# nixie_tube.net
KiCad netlist of a schematic drawn in Altium Designer
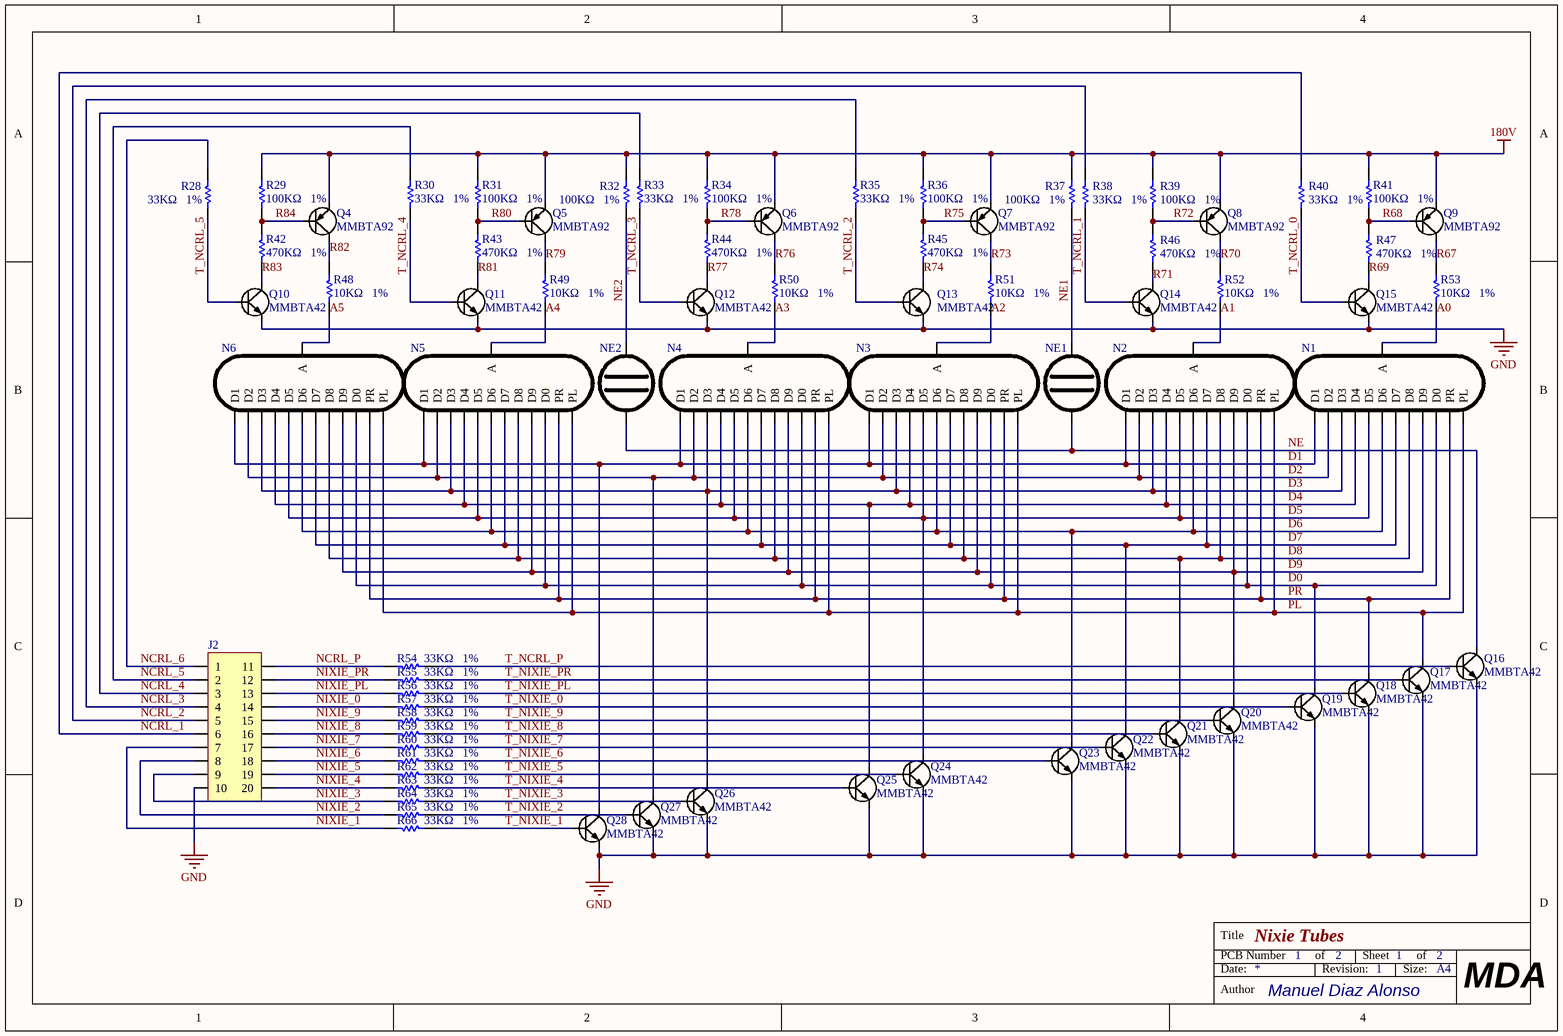
[diagram p0: nixie_tube.SchDoc]

(export (version "E")
  (design (tool "Eeschema 10.0.6"))
  (components
    (comp (ref "J2")
      (value "PIN_2X10")
      (footprint "PIN_2X10_HDR")
      (description "TSW-110-15-F-D-LL")
      (libsource (lib "Nixielib") (part "PIN_2X10"))
    )
    (comp (ref "N1")
      (value "NIXIE-IN14")
      (footprint "NIXIE_IN-14")
      (libsource (lib "MyLib") (part "NIXIE-IN14"))
    )
    (comp (ref "N2")
      (value "NIXIE-IN14")
      (footprint "NIXIE_IN-14")
      (libsource (lib "MyLib") (part "NIXIE-IN14"))
    )
    (comp (ref "N3")
      (value "NIXIE-IN14")
      (footprint "NIXIE_IN-14")
      (libsource (lib "MyLib") (part "NIXIE-IN14"))
    )
    (comp (ref "N4")
      (value "NIXIE-IN14")
      (footprint "NIXIE_IN-14")
      (libsource (lib "MyLib") (part "NIXIE-IN14"))
    )
    (comp (ref "N5")
      (value "NIXIE-IN14")
      (footprint "NIXIE_IN-14")
      (libsource (lib "MyLib") (part "NIXIE-IN14"))
    )
    (comp (ref "N6")
      (value "NIXIE-IN14")
      (footprint "NIXIE_IN-14")
      (libsource (lib "MyLib") (part "NIXIE-IN14"))
    )
    (comp (ref "NE1")
      (value "NIXIE-IN3")
      (footprint "NIXIE_IN-3")
      (libsource (lib "MyLib") (part "NIXIE-IN3"))
    )
    (comp (ref "NE2")
      (value "NIXIE-IN3")
      (footprint "NIXIE_IN-3")
      (libsource (lib "MyLib") (part "NIXIE-IN3"))
    )
    (comp (ref "Q4") (value "MMBTA92") (footprint "SOT-23") (libsource (lib "Nixielib") (part "PNP")))
    (comp (ref "Q5") (value "MMBTA92") (footprint "SOT-23") (libsource (lib "Nixielib") (part "PNP")))
    (comp (ref "Q6") (value "MMBTA92") (footprint "SOT-23") (libsource (lib "Nixielib") (part "PNP")))
    (comp (ref "Q7") (value "MMBTA92") (footprint "SOT-23") (libsource (lib "Nixielib") (part "PNP")))
    (comp (ref "Q8") (value "MMBTA92") (footprint "SOT-23") (libsource (lib "Nixielib") (part "PNP")))
    (comp (ref "Q9") (value "MMBTA92") (footprint "SOT-23") (libsource (lib "Nixielib") (part "PNP")))
    (comp (ref "Q10") (value "MMBTA42") (footprint "SOT-23") (libsource (lib "Nixielib") (part "NPN")))
    (comp (ref "Q11") (value "MMBTA42") (footprint "SOT-23") (libsource (lib "Nixielib") (part "NPN")))
    (comp (ref "Q12") (value "MMBTA42") (footprint "SOT-23") (libsource (lib "Nixielib") (part "NPN")))
    (comp (ref "Q13") (value "MMBTA42") (footprint "SOT-23") (libsource (lib "Nixielib") (part "NPN")))
    (comp (ref "Q14") (value "MMBTA42") (footprint "SOT-23") (libsource (lib "Nixielib") (part "NPN")))
    (comp (ref "Q15") (value "MMBTA42") (footprint "SOT-23") (libsource (lib "Nixielib") (part "NPN")))
    (comp (ref "Q16") (value "MMBTA42") (footprint "SOT-23") (libsource (lib "Nixielib") (part "NPN")))
    (comp (ref "Q17") (value "MMBTA42") (footprint "SOT-23") (libsource (lib "Nixielib") (part "NPN")))
    (comp (ref "Q18") (value "MMBTA42") (footprint "SOT-23") (libsource (lib "Nixielib") (part "NPN")))
    (comp (ref "Q19") (value "MMBTA42") (footprint "SOT-23") (libsource (lib "Nixielib") (part "NPN")))
    (comp (ref "Q20") (value "MMBTA42") (footprint "SOT-23") (libsource (lib "Nixielib") (part "NPN")))
    (comp (ref "Q21") (value "MMBTA42") (footprint "SOT-23") (libsource (lib "Nixielib") (part "NPN")))
    (comp (ref "Q22") (value "MMBTA42") (footprint "SOT-23") (libsource (lib "Nixielib") (part "NPN")))
    (comp (ref "Q23") (value "MMBTA42") (footprint "SOT-23") (libsource (lib "Nixielib") (part "NPN")))
    (comp (ref "Q24") (value "MMBTA42") (footprint "SOT-23") (libsource (lib "Nixielib") (part "NPN")))
    (comp (ref "Q25") (value "MMBTA42") (footprint "SOT-23") (libsource (lib "Nixielib") (part "NPN")))
    (comp (ref "Q26") (value "MMBTA42") (footprint "SOT-23") (libsource (lib "Nixielib") (part "NPN")))
    (comp (ref "Q27") (value "MMBTA42") (footprint "SOT-23") (libsource (lib "Nixielib") (part "NPN")))
    (comp (ref "Q28") (value "MMBTA42") (footprint "SOT-23") (libsource (lib "Nixielib") (part "NPN")))
    (comp (ref "R28") (value "33KΩ   1%") (footprint "0603") (libsource (lib "Nixielib") (part "RES")))
    (comp (ref "R29") (value "100KΩ   1%") (footprint "0603") (libsource (lib "Nixielib") (part "RES")))
    (comp (ref "R30") (value "33KΩ   1%") (footprint "0603") (libsource (lib "Nixielib") (part "RES")))
    (comp (ref "R31") (value "100KΩ   1%") (footprint "0603") (libsource (lib "Nixielib") (part "RES")))
    (comp (ref "R32") (value "100KΩ   1%") (footprint "0603") (libsource (lib "Nixielib") (part "RES")))
    (comp (ref "R33") (value "33KΩ   1%") (footprint "0603") (libsource (lib "Nixielib") (part "RES")))
    (comp (ref "R34") (value "100KΩ   1%") (footprint "0603") (libsource (lib "Nixielib") (part "RES")))
    (comp (ref "R35") (value "33KΩ   1%") (footprint "0603") (libsource (lib "Nixielib") (part "RES")))
    (comp (ref "R36") (value "100KΩ   1%") (footprint "0603") (libsource (lib "Nixielib") (part "RES")))
    (comp (ref "R37") (value "100KΩ   1%") (footprint "0603") (libsource (lib "Nixielib") (part "RES")))
    (comp (ref "R38") (value "33KΩ   1%") (footprint "0603") (libsource (lib "Nixielib") (part "RES")))
    (comp (ref "R39") (value "100KΩ   1%") (footprint "0603") (libsource (lib "Nixielib") (part "RES")))
    (comp (ref "R40") (value "33KΩ   1%") (footprint "0603") (libsource (lib "Nixielib") (part "RES")))
    (comp (ref "R41") (value "100KΩ   1%") (footprint "0603") (libsource (lib "Nixielib") (part "RES")))
    (comp (ref "R42") (value "470KΩ   1%") (footprint "0603") (libsource (lib "Nixielib") (part "RES")))
    (comp (ref "R43") (value "470KΩ   1%") (footprint "0603") (libsource (lib "Nixielib") (part "RES")))
    (comp (ref "R44") (value "470KΩ   1%") (footprint "0603") (libsource (lib "Nixielib") (part "RES")))
    (comp (ref "R45") (value "470KΩ   1%") (footprint "0603") (libsource (lib "Nixielib") (part "RES")))
    (comp (ref "R46") (value "470KΩ   1%") (footprint "0603") (libsource (lib "Nixielib") (part "RES")))
    (comp (ref "R47") (value "470KΩ   1%") (footprint "0603") (libsource (lib "Nixielib") (part "RES")))
    (comp (ref "R48") (value "10KΩ   1%") (footprint "0603") (libsource (lib "Nixielib") (part "RES")))
    (comp (ref "R49") (value "10KΩ   1%") (footprint "0603") (libsource (lib "Nixielib") (part "RES")))
    (comp (ref "R50") (value "10KΩ   1%") (footprint "0603") (libsource (lib "Nixielib") (part "RES")))
    (comp (ref "R51") (value "10KΩ   1%") (footprint "0603") (libsource (lib "Nixielib") (part "RES")))
    (comp (ref "R52") (value "10KΩ   1%") (footprint "0603") (libsource (lib "Nixielib") (part "RES")))
    (comp (ref "R53") (value "10KΩ   1%") (footprint "0603") (libsource (lib "Nixielib") (part "RES")))
    (comp (ref "R54") (value "33KΩ   1%") (footprint "0603") (libsource (lib "Nixielib") (part "RES")))
    (comp (ref "R55") (value "33KΩ   1%") (footprint "0603") (libsource (lib "Nixielib") (part "RES")))
    (comp (ref "R56") (value "33KΩ   1%") (footprint "0603") (libsource (lib "Nixielib") (part "RES")))
    (comp (ref "R57") (value "33KΩ   1%") (footprint "0603") (libsource (lib "Nixielib") (part "RES")))
    (comp (ref "R58") (value "33KΩ   1%") (footprint "0603") (libsource (lib "Nixielib") (part "RES")))
    (comp (ref "R59") (value "33KΩ   1%") (footprint "0603") (libsource (lib "Nixielib") (part "RES")))
    (comp (ref "R60") (value "33KΩ   1%") (footprint "0603") (libsource (lib "Nixielib") (part "RES")))
    (comp (ref "R61") (value "33KΩ   1%") (footprint "0603") (libsource (lib "Nixielib") (part "RES")))
    (comp (ref "R62") (value "33KΩ   1%") (footprint "0603") (libsource (lib "Nixielib") (part "RES")))
    (comp (ref "R63") (value "33KΩ   1%") (footprint "0603") (libsource (lib "Nixielib") (part "RES")))
    (comp (ref "R64") (value "33KΩ   1%") (footprint "0603") (libsource (lib "Nixielib") (part "RES")))
    (comp (ref "R65") (value "33KΩ   1%") (footprint "0603") (libsource (lib "Nixielib") (part "RES")))
    (comp (ref "R66") (value "33KΩ   1%") (footprint "0603") (libsource (lib "Nixielib") (part "RES")))
  )
  (nets
    (net (code "1") (name "/A0") (class "Default")
      (node (ref "N1") (pin "1") (pinfunction "A_1") (pintype "passive"))
      (node (ref "R53") (pin "1") (pinfunction "1_1") (pintype "passive"))
    )
    (net (code "2") (name "/A1") (class "Default")
      (node (ref "N2") (pin "1") (pinfunction "A_1") (pintype "passive"))
      (node (ref "R52") (pin "1") (pinfunction "1_1") (pintype "passive"))
    )
    (net (code "3") (name "/A2") (class "Default")
      (node (ref "N3") (pin "1") (pinfunction "A_1") (pintype "passive"))
      (node (ref "R51") (pin "1") (pinfunction "1_1") (pintype "passive"))
    )
    (net (code "4") (name "/A3") (class "Default")
      (node (ref "N4") (pin "1") (pinfunction "A_1") (pintype "passive"))
      (node (ref "R50") (pin "1") (pinfunction "1_1") (pintype "passive"))
    )
    (net (code "5") (name "/A4") (class "Default")
      (node (ref "N5") (pin "1") (pinfunction "A_1") (pintype "passive"))
      (node (ref "R49") (pin "1") (pinfunction "1_1") (pintype "passive"))
    )
    (net (code "6") (name "/A5") (class "Default")
      (node (ref "N6") (pin "1") (pinfunction "A_1") (pintype "passive"))
      (node (ref "R48") (pin "1") (pinfunction "1_1") (pintype "passive"))
    )
    (net (code "7") (name "/D0") (class "Default")
      (node (ref "N1") (pin "12") (pinfunction "D0_12") (pintype "passive"))
      (node (ref "N2") (pin "12") (pinfunction "D0_12") (pintype "passive"))
      (node (ref "N3") (pin "12") (pinfunction "D0_12") (pintype "passive"))
      (node (ref "N4") (pin "12") (pinfunction "D0_12") (pintype "passive"))
      (node (ref "N5") (pin "12") (pinfunction "D0_12") (pintype "passive"))
      (node (ref "N6") (pin "12") (pinfunction "D0_12") (pintype "passive"))
      (node (ref "Q19") (pin "3") (pinfunction "C_3") (pintype "passive"))
    )
    (net (code "8") (name "/D1") (class "Default")
      (node (ref "N1") (pin "3") (pinfunction "D1_3") (pintype "passive"))
      (node (ref "N2") (pin "3") (pinfunction "D1_3") (pintype "passive"))
      (node (ref "N3") (pin "3") (pinfunction "D1_3") (pintype "passive"))
      (node (ref "N4") (pin "3") (pinfunction "D1_3") (pintype "passive"))
      (node (ref "N5") (pin "3") (pinfunction "D1_3") (pintype "passive"))
      (node (ref "N6") (pin "3") (pinfunction "D1_3") (pintype "passive"))
      (node (ref "Q28") (pin "3") (pinfunction "C_3") (pintype "passive"))
    )
    (net (code "9") (name "/D2") (class "Default")
      (node (ref "N1") (pin "4") (pinfunction "D2_4") (pintype "passive"))
      (node (ref "N2") (pin "4") (pinfunction "D2_4") (pintype "passive"))
      (node (ref "N3") (pin "4") (pinfunction "D2_4") (pintype "passive"))
      (node (ref "N4") (pin "4") (pinfunction "D2_4") (pintype "passive"))
      (node (ref "N5") (pin "4") (pinfunction "D2_4") (pintype "passive"))
      (node (ref "N6") (pin "4") (pinfunction "D2_4") (pintype "passive"))
      (node (ref "Q27") (pin "3") (pinfunction "C_3") (pintype "passive"))
    )
    (net (code "10") (name "/D3") (class "Default")
      (node (ref "N1") (pin "5") (pinfunction "D3_5") (pintype "passive"))
      (node (ref "N2") (pin "5") (pinfunction "D3_5") (pintype "passive"))
      (node (ref "N3") (pin "5") (pinfunction "D3_5") (pintype "passive"))
      (node (ref "N4") (pin "5") (pinfunction "D3_5") (pintype "passive"))
      (node (ref "N5") (pin "5") (pinfunction "D3_5") (pintype "passive"))
      (node (ref "N6") (pin "5") (pinfunction "D3_5") (pintype "passive"))
      (node (ref "Q26") (pin "3") (pinfunction "C_3") (pintype "passive"))
    )
    (net (code "11") (name "/D4") (class "Default")
      (node (ref "N1") (pin "6") (pinfunction "D4_6") (pintype "passive"))
      (node (ref "N2") (pin "6") (pinfunction "D4_6") (pintype "passive"))
      (node (ref "N3") (pin "6") (pinfunction "D4_6") (pintype "passive"))
      (node (ref "N4") (pin "6") (pinfunction "D4_6") (pintype "passive"))
      (node (ref "N5") (pin "6") (pinfunction "D4_6") (pintype "passive"))
      (node (ref "N6") (pin "6") (pinfunction "D4_6") (pintype "passive"))
      (node (ref "Q25") (pin "3") (pinfunction "C_3") (pintype "passive"))
    )
    (net (code "12") (name "/D5") (class "Default")
      (node (ref "N1") (pin "7") (pinfunction "D5_7") (pintype "passive"))
      (node (ref "N2") (pin "7") (pinfunction "D5_7") (pintype "passive"))
      (node (ref "N3") (pin "7") (pinfunction "D5_7") (pintype "passive"))
      (node (ref "N4") (pin "7") (pinfunction "D5_7") (pintype "passive"))
      (node (ref "N5") (pin "7") (pinfunction "D5_7") (pintype "passive"))
      (node (ref "N6") (pin "7") (pinfunction "D5_7") (pintype "passive"))
      (node (ref "Q24") (pin "3") (pinfunction "C_3") (pintype "passive"))
    )
    (net (code "13") (name "/D6") (class "Default")
      (node (ref "N1") (pin "8") (pinfunction "D6_8") (pintype "passive"))
      (node (ref "N2") (pin "8") (pinfunction "D6_8") (pintype "passive"))
      (node (ref "N3") (pin "8") (pinfunction "D6_8") (pintype "passive"))
      (node (ref "N4") (pin "8") (pinfunction "D6_8") (pintype "passive"))
      (node (ref "N5") (pin "8") (pinfunction "D6_8") (pintype "passive"))
      (node (ref "N6") (pin "8") (pinfunction "D6_8") (pintype "passive"))
      (node (ref "Q23") (pin "3") (pinfunction "C_3") (pintype "passive"))
    )
    (net (code "14") (name "/D7") (class "Default")
      (node (ref "N1") (pin "9") (pinfunction "D7_9") (pintype "passive"))
      (node (ref "N2") (pin "9") (pinfunction "D7_9") (pintype "passive"))
      (node (ref "N3") (pin "9") (pinfunction "D7_9") (pintype "passive"))
      (node (ref "N4") (pin "9") (pinfunction "D7_9") (pintype "passive"))
      (node (ref "N5") (pin "9") (pinfunction "D7_9") (pintype "passive"))
      (node (ref "N6") (pin "9") (pinfunction "D7_9") (pintype "passive"))
      (node (ref "Q22") (pin "3") (pinfunction "C_3") (pintype "passive"))
    )
    (net (code "15") (name "/D8") (class "Default")
      (node (ref "N1") (pin "10") (pinfunction "D8_10") (pintype "passive"))
      (node (ref "N2") (pin "10") (pinfunction "D8_10") (pintype "passive"))
      (node (ref "N3") (pin "10") (pinfunction "D8_10") (pintype "passive"))
      (node (ref "N4") (pin "10") (pinfunction "D8_10") (pintype "passive"))
      (node (ref "N5") (pin "10") (pinfunction "D8_10") (pintype "passive"))
      (node (ref "N6") (pin "10") (pinfunction "D8_10") (pintype "passive"))
      (node (ref "Q21") (pin "3") (pinfunction "C_3") (pintype "passive"))
    )
    (net (code "16") (name "/D9") (class "Default")
      (node (ref "N1") (pin "11") (pinfunction "D9_11") (pintype "passive"))
      (node (ref "N2") (pin "11") (pinfunction "D9_11") (pintype "passive"))
      (node (ref "N3") (pin "11") (pinfunction "D9_11") (pintype "passive"))
      (node (ref "N4") (pin "11") (pinfunction "D9_11") (pintype "passive"))
      (node (ref "N5") (pin "11") (pinfunction "D9_11") (pintype "passive"))
      (node (ref "N6") (pin "11") (pinfunction "D9_11") (pintype "passive"))
      (node (ref "Q20") (pin "3") (pinfunction "C_3") (pintype "passive"))
    )
    (net (code "17") (name "/NCRL_1") (class "Default")
      (node (ref "J2") (pin "6") (pinfunction "6_6") (pintype "passive"))
      (node (ref "R40") (pin "1") (pinfunction "1_1") (pintype "passive"))
    )
    (net (code "18") (name "/NCRL_2") (class "Default")
      (node (ref "J2") (pin "5") (pinfunction "5_5") (pintype "passive"))
      (node (ref "R38") (pin "2") (pinfunction "2_2") (pintype "passive"))
    )
    (net (code "19") (name "/NCRL_3") (class "Default")
      (node (ref "J2") (pin "4") (pinfunction "4_4") (pintype "passive"))
      (node (ref "R35") (pin "2") (pinfunction "2_2") (pintype "passive"))
    )
    (net (code "20") (name "/NCRL_4") (class "Default")
      (node (ref "J2") (pin "3") (pinfunction "3_3") (pintype "passive"))
      (node (ref "R33") (pin "1") (pinfunction "1_1") (pintype "passive"))
    )
    (net (code "21") (name "/NCRL_5") (class "Default")
      (node (ref "J2") (pin "2") (pinfunction "2_2") (pintype "passive"))
      (node (ref "R30") (pin "2") (pinfunction "2_2") (pintype "passive"))
    )
    (net (code "22") (name "/NCRL_6") (class "Default")
      (node (ref "J2") (pin "1") (pinfunction "1_1") (pintype "passive"))
      (node (ref "R28") (pin "2") (pinfunction "2_2") (pintype "passive"))
    )
    (net (code "23") (name "/NCRL_P") (class "Default")
      (node (ref "J2") (pin "11") (pinfunction "11_11") (pintype "passive"))
      (node (ref "R54") (pin "1") (pinfunction "1_1") (pintype "passive"))
    )
    (net (code "24") (name "/NE") (class "Default")
      (node (ref "NE1") (pin "2") (pinfunction "2_2") (pintype "passive"))
      (node (ref "NE2") (pin "2") (pinfunction "2_2") (pintype "passive"))
      (node (ref "Q16") (pin "3") (pinfunction "C_3") (pintype "passive"))
    )
    (net (code "25") (name "/NE1") (class "Default")
      (node (ref "NE1") (pin "1") (pinfunction "1_1") (pintype "passive"))
      (node (ref "R37") (pin "1") (pinfunction "1_1") (pintype "passive"))
    )
    (net (code "26") (name "/NE2") (class "Default")
      (node (ref "NE2") (pin "1") (pinfunction "1_1") (pintype "passive"))
      (node (ref "R32") (pin "1") (pinfunction "1_1") (pintype "passive"))
    )
    (net (code "27") (name "/NIXIE_0") (class "Default")
      (node (ref "J2") (pin "14") (pinfunction "14_14") (pintype "passive"))
      (node (ref "R57") (pin "1") (pinfunction "1_1") (pintype "passive"))
    )
    (net (code "28") (name "/NIXIE_1") (class "Default")
      (node (ref "J2") (pin "7") (pinfunction "7_7") (pintype "passive"))
      (node (ref "R66") (pin "1") (pinfunction "1_1") (pintype "passive"))
    )
    (net (code "29") (name "/NIXIE_2") (class "Default")
      (node (ref "J2") (pin "8") (pinfunction "8_8") (pintype "passive"))
      (node (ref "R65") (pin "1") (pinfunction "1_1") (pintype "passive"))
    )
    (net (code "30") (name "/NIXIE_3") (class "Default")
      (node (ref "J2") (pin "9") (pinfunction "9_9") (pintype "passive"))
      (node (ref "R64") (pin "1") (pinfunction "1_1") (pintype "passive"))
    )
    (net (code "31") (name "/NIXIE_4") (class "Default")
      (node (ref "J2") (pin "20") (pinfunction "20_20") (pintype "passive"))
      (node (ref "R63") (pin "1") (pinfunction "1_1") (pintype "passive"))
    )
    (net (code "32") (name "/NIXIE_5") (class "Default")
      (node (ref "J2") (pin "19") (pinfunction "19_19") (pintype "passive"))
      (node (ref "R62") (pin "1") (pinfunction "1_1") (pintype "passive"))
    )
    (net (code "33") (name "/NIXIE_6") (class "Default")
      (node (ref "J2") (pin "18") (pinfunction "18_18") (pintype "passive"))
      (node (ref "R61") (pin "1") (pinfunction "1_1") (pintype "passive"))
    )
    (net (code "34") (name "/NIXIE_7") (class "Default")
      (node (ref "J2") (pin "17") (pinfunction "17_17") (pintype "passive"))
      (node (ref "R60") (pin "1") (pinfunction "1_1") (pintype "passive"))
    )
    (net (code "35") (name "/NIXIE_8") (class "Default")
      (node (ref "J2") (pin "16") (pinfunction "16_16") (pintype "passive"))
      (node (ref "R59") (pin "1") (pinfunction "1_1") (pintype "passive"))
    )
    (net (code "36") (name "/NIXIE_9") (class "Default")
      (node (ref "J2") (pin "15") (pinfunction "15_15") (pintype "passive"))
      (node (ref "R58") (pin "1") (pinfunction "1_1") (pintype "passive"))
    )
    (net (code "37") (name "/NIXIE_PL") (class "Default")
      (node (ref "J2") (pin "13") (pinfunction "13_13") (pintype "passive"))
      (node (ref "R56") (pin "1") (pinfunction "1_1") (pintype "passive"))
    )
    (net (code "38") (name "/NIXIE_PR") (class "Default")
      (node (ref "J2") (pin "12") (pinfunction "12_12") (pintype "passive"))
      (node (ref "R55") (pin "1") (pinfunction "1_1") (pintype "passive"))
    )
    (net (code "39") (name "/PL") (class "Default")
      (node (ref "N1") (pin "2") (pinfunction "PL_2") (pintype "passive"))
      (node (ref "N2") (pin "2") (pinfunction "PL_2") (pintype "passive"))
      (node (ref "N3") (pin "2") (pinfunction "PL_2") (pintype "passive"))
      (node (ref "N4") (pin "2") (pinfunction "PL_2") (pintype "passive"))
      (node (ref "N5") (pin "2") (pinfunction "PL_2") (pintype "passive"))
      (node (ref "N6") (pin "2") (pinfunction "PL_2") (pintype "passive"))
      (node (ref "Q17") (pin "3") (pinfunction "C_3") (pintype "passive"))
    )
    (net (code "40") (name "/PR") (class "Default")
      (node (ref "N1") (pin "13") (pinfunction "PR_13") (pintype "passive"))
      (node (ref "N2") (pin "13") (pinfunction "PR_13") (pintype "passive"))
      (node (ref "N3") (pin "13") (pinfunction "PR_13") (pintype "passive"))
      (node (ref "N4") (pin "13") (pinfunction "PR_13") (pintype "passive"))
      (node (ref "N5") (pin "13") (pinfunction "PR_13") (pintype "passive"))
      (node (ref "N6") (pin "13") (pinfunction "PR_13") (pintype "passive"))
      (node (ref "Q18") (pin "3") (pinfunction "C_3") (pintype "passive"))
    )
    (net (code "41") (name "/R67") (class "Default")
      (node (ref "Q9") (pin "3") (pinfunction "C_3") (pintype "passive"))
      (node (ref "R53") (pin "2") (pinfunction "2_2") (pintype "passive"))
    )
    (net (code "42") (name "/R68") (class "Default")
      (node (ref "Q9") (pin "1") (pinfunction "B_1") (pintype "passive"))
      (node (ref "R41") (pin "1") (pinfunction "1_1") (pintype "passive"))
      (node (ref "R47") (pin "2") (pinfunction "2_2") (pintype "passive"))
    )
    (net (code "43") (name "/R69") (class "Default")
      (node (ref "Q15") (pin "3") (pinfunction "C_3") (pintype "passive"))
      (node (ref "R47") (pin "1") (pinfunction "1_1") (pintype "passive"))
    )
    (net (code "44") (name "/R70") (class "Default")
      (node (ref "Q8") (pin "3") (pinfunction "C_3") (pintype "passive"))
      (node (ref "R52") (pin "2") (pinfunction "2_2") (pintype "passive"))
    )
    (net (code "45") (name "/R71") (class "Default")
      (node (ref "Q14") (pin "3") (pinfunction "C_3") (pintype "passive"))
      (node (ref "R46") (pin "1") (pinfunction "1_1") (pintype "passive"))
    )
    (net (code "46") (name "/R72") (class "Default")
      (node (ref "Q8") (pin "1") (pinfunction "B_1") (pintype "passive"))
      (node (ref "R39") (pin "1") (pinfunction "1_1") (pintype "passive"))
      (node (ref "R46") (pin "2") (pinfunction "2_2") (pintype "passive"))
    )
    (net (code "47") (name "/R73") (class "Default")
      (node (ref "Q7") (pin "3") (pinfunction "C_3") (pintype "passive"))
      (node (ref "R51") (pin "2") (pinfunction "2_2") (pintype "passive"))
    )
    (net (code "48") (name "/R74") (class "Default")
      (node (ref "Q13") (pin "3") (pinfunction "C_3") (pintype "passive"))
      (node (ref "R45") (pin "1") (pinfunction "1_1") (pintype "passive"))
    )
    (net (code "49") (name "/R75") (class "Default")
      (node (ref "Q7") (pin "1") (pinfunction "B_1") (pintype "passive"))
      (node (ref "R36") (pin "1") (pinfunction "1_1") (pintype "passive"))
      (node (ref "R45") (pin "2") (pinfunction "2_2") (pintype "passive"))
    )
    (net (code "50") (name "/R76") (class "Default")
      (node (ref "Q6") (pin "3") (pinfunction "C_3") (pintype "passive"))
      (node (ref "R50") (pin "2") (pinfunction "2_2") (pintype "passive"))
    )
    (net (code "51") (name "/R77") (class "Default")
      (node (ref "Q12") (pin "3") (pinfunction "C_3") (pintype "passive"))
      (node (ref "R44") (pin "1") (pinfunction "1_1") (pintype "passive"))
    )
    (net (code "52") (name "/R78") (class "Default")
      (node (ref "Q6") (pin "1") (pinfunction "B_1") (pintype "passive"))
      (node (ref "R34") (pin "1") (pinfunction "1_1") (pintype "passive"))
      (node (ref "R44") (pin "2") (pinfunction "2_2") (pintype "passive"))
    )
    (net (code "53") (name "/R79") (class "Default")
      (node (ref "Q5") (pin "3") (pinfunction "C_3") (pintype "passive"))
      (node (ref "R49") (pin "2") (pinfunction "2_2") (pintype "passive"))
    )
    (net (code "54") (name "/R80") (class "Default")
      (node (ref "Q5") (pin "1") (pinfunction "B_1") (pintype "passive"))
      (node (ref "R31") (pin "1") (pinfunction "1_1") (pintype "passive"))
      (node (ref "R43") (pin "2") (pinfunction "2_2") (pintype "passive"))
    )
    (net (code "55") (name "/R81") (class "Default")
      (node (ref "Q11") (pin "3") (pinfunction "C_3") (pintype "passive"))
      (node (ref "R43") (pin "1") (pinfunction "1_1") (pintype "passive"))
    )
    (net (code "56") (name "/R82") (class "Default")
      (node (ref "Q4") (pin "3") (pinfunction "C_3") (pintype "passive"))
      (node (ref "R48") (pin "2") (pinfunction "2_2") (pintype "passive"))
    )
    (net (code "57") (name "/R83") (class "Default")
      (node (ref "Q10") (pin "3") (pinfunction "C_3") (pintype "passive"))
      (node (ref "R42") (pin "1") (pinfunction "1_1") (pintype "passive"))
    )
    (net (code "58") (name "/R84") (class "Default")
      (node (ref "Q4") (pin "1") (pinfunction "B_1") (pintype "passive"))
      (node (ref "R29") (pin "1") (pinfunction "1_1") (pintype "passive"))
      (node (ref "R42") (pin "2") (pinfunction "2_2") (pintype "passive"))
    )
    (net (code "59") (name "/T_NCRL_0") (class "Default")
      (node (ref "Q15") (pin "1") (pinfunction "B_1") (pintype "passive"))
      (node (ref "R40") (pin "2") (pinfunction "2_2") (pintype "passive"))
    )
    (net (code "60") (name "/T_NCRL_1") (class "Default")
      (node (ref "Q14") (pin "1") (pinfunction "B_1") (pintype "passive"))
      (node (ref "R38") (pin "1") (pinfunction "1_1") (pintype "passive"))
    )
    (net (code "61") (name "/T_NCRL_2") (class "Default")
      (node (ref "Q13") (pin "1") (pinfunction "B_1") (pintype "passive"))
      (node (ref "R35") (pin "1") (pinfunction "1_1") (pintype "passive"))
    )
    (net (code "62") (name "/T_NCRL_3") (class "Default")
      (node (ref "Q12") (pin "1") (pinfunction "B_1") (pintype "passive"))
      (node (ref "R33") (pin "2") (pinfunction "2_2") (pintype "passive"))
    )
    (net (code "63") (name "/T_NCRL_4") (class "Default")
      (node (ref "Q11") (pin "1") (pinfunction "B_1") (pintype "passive"))
      (node (ref "R30") (pin "1") (pinfunction "1_1") (pintype "passive"))
    )
    (net (code "64") (name "/T_NCRL_5") (class "Default")
      (node (ref "Q10") (pin "1") (pinfunction "B_1") (pintype "passive"))
      (node (ref "R28") (pin "1") (pinfunction "1_1") (pintype "passive"))
    )
    (net (code "65") (name "/T_NCRL_P") (class "Default")
      (node (ref "Q16") (pin "1") (pinfunction "B_1") (pintype "passive"))
      (node (ref "R54") (pin "2") (pinfunction "2_2") (pintype "passive"))
    )
    (net (code "66") (name "/T_NIXIE_0") (class "Default")
      (node (ref "Q19") (pin "1") (pinfunction "B_1") (pintype "passive"))
      (node (ref "R57") (pin "2") (pinfunction "2_2") (pintype "passive"))
    )
    (net (code "67") (name "/T_NIXIE_1") (class "Default")
      (node (ref "Q28") (pin "1") (pinfunction "B_1") (pintype "passive"))
      (node (ref "R66") (pin "2") (pinfunction "2_2") (pintype "passive"))
    )
    (net (code "68") (name "/T_NIXIE_2") (class "Default")
      (node (ref "Q27") (pin "1") (pinfunction "B_1") (pintype "passive"))
      (node (ref "R65") (pin "2") (pinfunction "2_2") (pintype "passive"))
    )
    (net (code "69") (name "/T_NIXIE_3") (class "Default")
      (node (ref "Q26") (pin "1") (pinfunction "B_1") (pintype "passive"))
      (node (ref "R64") (pin "2") (pinfunction "2_2") (pintype "passive"))
    )
    (net (code "70") (name "/T_NIXIE_4") (class "Default")
      (node (ref "Q25") (pin "1") (pinfunction "B_1") (pintype "passive"))
      (node (ref "R63") (pin "2") (pinfunction "2_2") (pintype "passive"))
    )
    (net (code "71") (name "/T_NIXIE_5") (class "Default")
      (node (ref "Q24") (pin "1") (pinfunction "B_1") (pintype "passive"))
      (node (ref "R62") (pin "2") (pinfunction "2_2") (pintype "passive"))
    )
    (net (code "72") (name "/T_NIXIE_6") (class "Default")
      (node (ref "Q23") (pin "1") (pinfunction "B_1") (pintype "passive"))
      (node (ref "R61") (pin "2") (pinfunction "2_2") (pintype "passive"))
    )
    (net (code "73") (name "/T_NIXIE_7") (class "Default")
      (node (ref "Q22") (pin "1") (pinfunction "B_1") (pintype "passive"))
      (node (ref "R60") (pin "2") (pinfunction "2_2") (pintype "passive"))
    )
    (net (code "74") (name "/T_NIXIE_8") (class "Default")
      (node (ref "Q21") (pin "1") (pinfunction "B_1") (pintype "passive"))
      (node (ref "R59") (pin "2") (pinfunction "2_2") (pintype "passive"))
    )
    (net (code "75") (name "/T_NIXIE_9") (class "Default")
      (node (ref "Q20") (pin "1") (pinfunction "B_1") (pintype "passive"))
      (node (ref "R58") (pin "2") (pinfunction "2_2") (pintype "passive"))
    )
    (net (code "76") (name "/T_NIXIE_PL") (class "Default")
      (node (ref "Q18") (pin "1") (pinfunction "B_1") (pintype "passive"))
      (node (ref "R56") (pin "2") (pinfunction "2_2") (pintype "passive"))
    )
    (net (code "77") (name "/T_NIXIE_PR") (class "Default")
      (node (ref "Q17") (pin "1") (pinfunction "B_1") (pintype "passive"))
      (node (ref "R55") (pin "2") (pinfunction "2_2") (pintype "passive"))
    )
    (net (code "78") (name "180V") (class "Default")
      (node (ref "Q4") (pin "2") (pinfunction "E_2") (pintype "passive"))
      (node (ref "Q5") (pin "2") (pinfunction "E_2") (pintype "passive"))
      (node (ref "Q6") (pin "2") (pinfunction "E_2") (pintype "passive"))
      (node (ref "Q7") (pin "2") (pinfunction "E_2") (pintype "passive"))
      (node (ref "Q8") (pin "2") (pinfunction "E_2") (pintype "passive"))
      (node (ref "Q9") (pin "2") (pinfunction "E_2") (pintype "passive"))
      (node (ref "R29") (pin "2") (pinfunction "2_2") (pintype "passive"))
      (node (ref "R31") (pin "2") (pinfunction "2_2") (pintype "passive"))
      (node (ref "R32") (pin "2") (pinfunction "2_2") (pintype "passive"))
      (node (ref "R34") (pin "2") (pinfunction "2_2") (pintype "passive"))
      (node (ref "R36") (pin "2") (pinfunction "2_2") (pintype "passive"))
      (node (ref "R37") (pin "2") (pinfunction "2_2") (pintype "passive"))
      (node (ref "R39") (pin "2") (pinfunction "2_2") (pintype "passive"))
      (node (ref "R41") (pin "2") (pinfunction "2_2") (pintype "passive"))
    )
    (net (code "79") (name "GND") (class "Default")
      (node (ref "J2") (pin "10") (pinfunction "10_10") (pintype "passive"))
      (node (ref "Q10") (pin "2") (pinfunction "E_2") (pintype "passive"))
      (node (ref "Q11") (pin "2") (pinfunction "E_2") (pintype "passive"))
      (node (ref "Q12") (pin "2") (pinfunction "E_2") (pintype "passive"))
      (node (ref "Q13") (pin "2") (pinfunction "E_2") (pintype "passive"))
      (node (ref "Q14") (pin "2") (pinfunction "E_2") (pintype "passive"))
      (node (ref "Q15") (pin "2") (pinfunction "E_2") (pintype "passive"))
      (node (ref "Q16") (pin "2") (pinfunction "E_2") (pintype "passive"))
      (node (ref "Q17") (pin "2") (pinfunction "E_2") (pintype "passive"))
      (node (ref "Q18") (pin "2") (pinfunction "E_2") (pintype "passive"))
      (node (ref "Q19") (pin "2") (pinfunction "E_2") (pintype "passive"))
      (node (ref "Q20") (pin "2") (pinfunction "E_2") (pintype "passive"))
      (node (ref "Q21") (pin "2") (pinfunction "E_2") (pintype "passive"))
      (node (ref "Q22") (pin "2") (pinfunction "E_2") (pintype "passive"))
      (node (ref "Q23") (pin "2") (pinfunction "E_2") (pintype "passive"))
      (node (ref "Q24") (pin "2") (pinfunction "E_2") (pintype "passive"))
      (node (ref "Q25") (pin "2") (pinfunction "E_2") (pintype "passive"))
      (node (ref "Q26") (pin "2") (pinfunction "E_2") (pintype "passive"))
      (node (ref "Q27") (pin "2") (pinfunction "E_2") (pintype "passive"))
      (node (ref "Q28") (pin "2") (pinfunction "E_2") (pintype "passive"))
    )
  )
)
